# MercurialSDR_MISC.net
KiCad netlist of a schematic drawn in Altium Designer
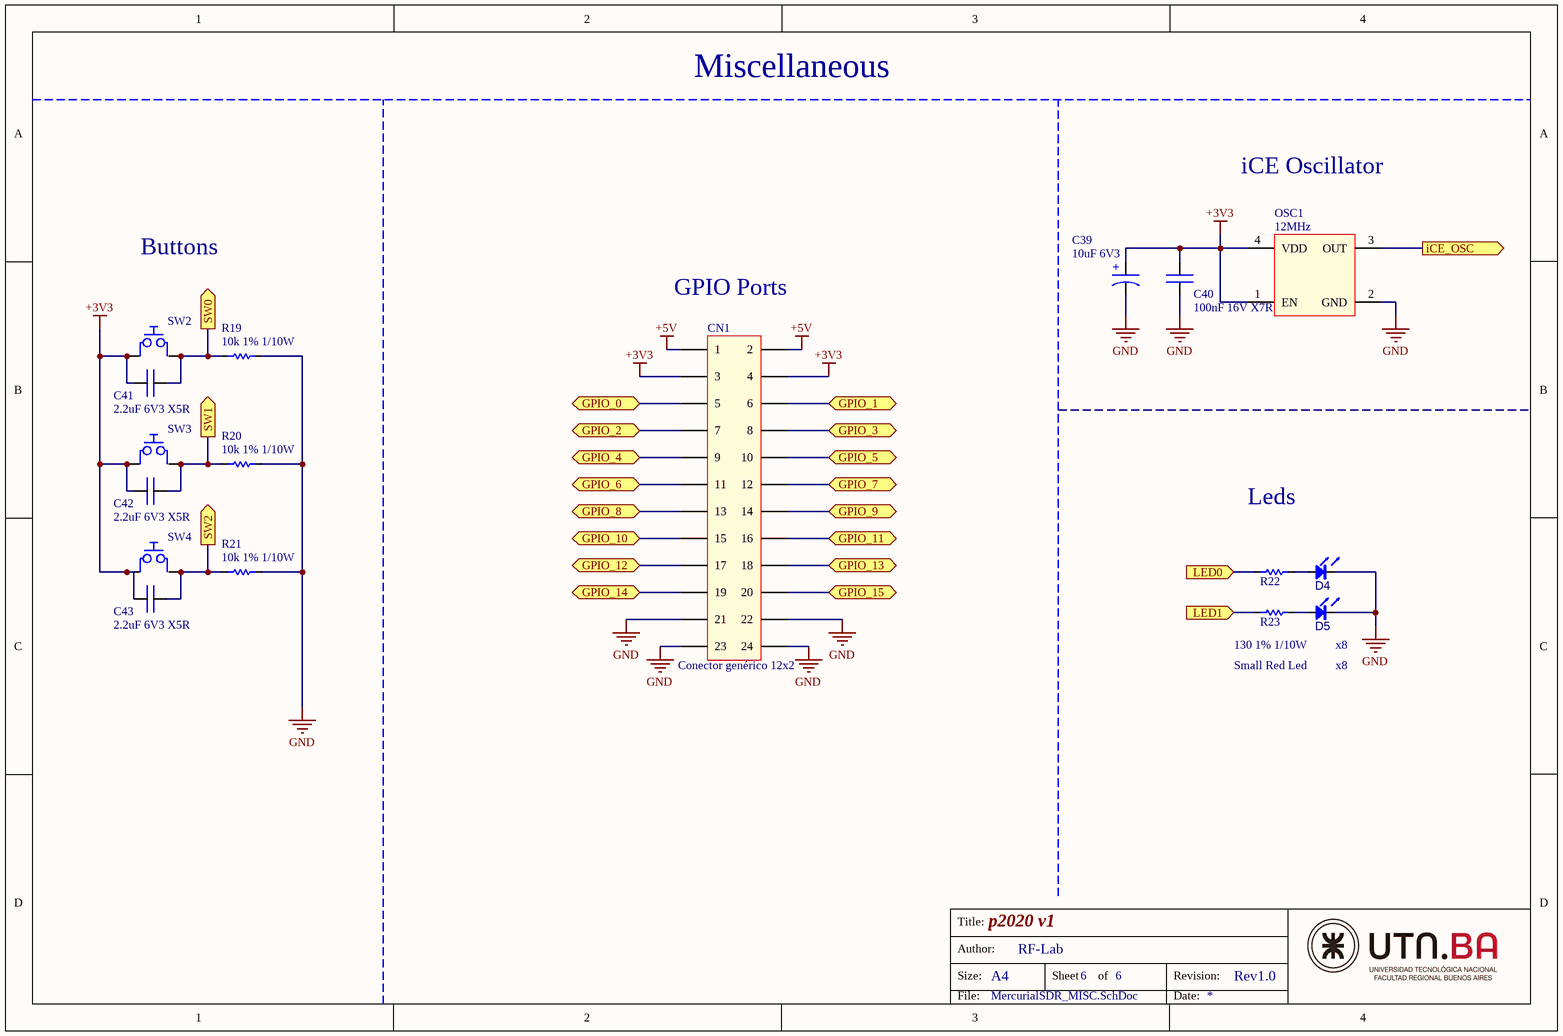
[diagram p0: MercurialSDR_MISC.SchDoc]

(export (version "E")
  (design (tool "Eeschema 10.0.6"))
  (components
    (comp (ref "C39")
      (value "10uF 6V3")
      (footprint "CAP_TANT_1206")
      (description "Capacitor polarizado")
      (fields (field (name "Comment") "10uF 6V3 - TAJA106K006RNJ"))
      (libsource (lib "MercurialSDR") (part "Cap Pol"))
    )
    (comp (ref "C40")
      (value "100nF 16V X7R")
      (footprint "CAP_0603")
      (description "Capacitor no polarizado")
      (fields
        (field (name "PART NUMBER") "CL10B104KO8NNNC")
        (field (name "Comment") "100nF 16V X7R - CL10B104KO8NNNC")
      )
      (libsource (lib "MercurialSDR") (part "Cap"))
    )
    (comp (ref "C41")
      (value "2.2uF 6V3 X5R")
      (footprint "CAP_0603")
      (description "Capacitor no polarizado")
      (fields (field (name "Comment") "2.2uF 6V3 X5R - CL10A225KQ8NNNC"))
      (libsource (lib "MercurialSDR") (part "Cap"))
    )
    (comp (ref "C42")
      (value "2.2uF 6V3 X5R")
      (footprint "CAP_0603")
      (description "Capacitor no polarizado")
      (fields
        (field (name "PART NUMBER") "CL10A225KQ8NNNC")
        (field (name "Comment") "2.2uF 6V3 X5R - CL10A225KQ8NNNC")
      )
      (libsource (lib "MercurialSDR") (part "Cap"))
    )
    (comp (ref "C43")
      (value "2.2uF 6V3 X5R")
      (footprint "CAP_0603")
      (description "Capacitor no polarizado")
      (fields
        (field (name "PART NUMBER") "CL10A225KQ8NNNC")
        (field (name "Comment") "2.2uF 6V3 X5R - CL10A225KQ8NNNC")
      )
      (libsource (lib "MercurialSDR") (part "Cap"))
    )
    (comp (ref "CN1")
      (value "Conector genérico 12x2")
      (footprint "CON_12x2")
      (fields (field (name "PART NUMBER") "6-534236-2") (field (name "Comment") "6-534236-2 // PPPC122LFBN"))
      (libsource (lib "MercurialSDR") (part "CN_12x2"))
    )
    (comp (ref "D4")
      (value "LTST-C190KRKT")
      (footprint "LED_0603")
      (description "Led_small")
      (libsource (lib "MercurialSDR") (part "Led_small"))
    )
    (comp (ref "D5")
      (value "LTST-C190KRKT")
      (footprint "LED_0603")
      (description "Led_small")
      (fields (field (name "COLOR") "Small Red Led"))
      (libsource (lib "MercurialSDR") (part "Led_small"))
    )
    (comp (ref "OSC1")
      (value "DSC6003JI2A-012.0000T")
      (footprint "VFLGA_2.5x2.0")
      (description "Oscilador de 4 terminales")
      (fields (field (name "FREQUENCY") "12MHz"))
      (libsource (lib "MercurialSDR") (part "Oscillator"))
    )
    (comp (ref "R19")
      (value "10k 1% 1/10W")
      (footprint "RES_0603")
      (description "Resistor")
      (fields (field (name "Comment") "10k 1% 1/10W - CR0603-FX-1002EAS"))
      (libsource (lib "MercurialSDR") (part "Res"))
    )
    (comp (ref "R20")
      (value "10k 1% 1/10W")
      (footprint "RES_0603")
      (description "Resistor")
      (fields (field (name "Comment") "10k 1% 1/10W - CR0603-FX-1002EAS"))
      (libsource (lib "MercurialSDR") (part "Res"))
    )
    (comp (ref "R21")
      (value "10k 1% 1/10W")
      (footprint "RES_0603")
      (description "Resistor")
      (fields (field (name "Comment") "10k 1% 1/10W - CR0603-FX-1002EAS"))
      (libsource (lib "MercurialSDR") (part "Res"))
    )
    (comp (ref "R22")
      (value "130 1% 1/10W - CR0603-FX-1300ELF")
      (footprint "RES_0603")
      (description "Resistor")
      (fields (field (name "POWER") "1/10W") (field (name "PART NUMBER") "CR0603-FX-1300ELF"))
      (libsource (lib "MercurialSDR") (part "Res"))
    )
    (comp (ref "R23")
      (value "130 1% 1/10W")
      (footprint "RES_0603")
      (description "Resistor")
      (fields (field (name "POWER") "1/10W") (field (name "PART NUMBER") "CR0603-FX-1300ELF"))
      (libsource (lib "MercurialSDR") (part "Res"))
    )
    (comp (ref "SW2")
      (value "PTS645SM43SMTR92 LFS")
      (footprint "SWITCH_6X6mm")
      (description "Pulsador")
      (libsource (lib "MercurialSDR") (part "Pulsador"))
    )
    (comp (ref "SW3")
      (value "PTS645SM43SMTR92 LFS")
      (footprint "SWITCH_6X6mm")
      (description "Pulsador")
      (libsource (lib "MercurialSDR") (part "Pulsador"))
    )
    (comp (ref "SW4")
      (value "PTS645SM43SMTR92 LFS")
      (footprint "SWITCH_6X6mm")
      (description "Pulsador")
      (libsource (lib "MercurialSDR") (part "Pulsador"))
    )
  )
  (nets
    (net (code "1") (name "+3V3") (class "Default")
      (node (ref "C39") (pin "1") (pinfunction "1_1") (pintype "passive"))
      (node (ref "C40") (pin "1") (pinfunction "1_1") (pintype "passive"))
      (node (ref "C41") (pin "1") (pinfunction "1_1") (pintype "passive"))
      (node (ref "C42") (pin "1") (pinfunction "1_1") (pintype "passive"))
      (node (ref "C43") (pin "1") (pinfunction "1_1") (pintype "passive"))
      (node (ref "CN1") (pin "3") (pinfunction "3_3") (pintype "passive"))
      (node (ref "CN1") (pin "4") (pinfunction "4_4") (pintype "passive"))
      (node (ref "OSC1") (pin "1") (pinfunction "EN_1") (pintype "passive"))
      (node (ref "OSC1") (pin "4") (pinfunction "VDD_4") (pintype "passive"))
      (node (ref "SW2") (pin "1") (pinfunction "1_1") (pintype "passive"))
      (node (ref "SW3") (pin "1") (pinfunction "1_1") (pintype "passive"))
      (node (ref "SW4") (pin "1") (pinfunction "1_1") (pintype "passive"))
    )
    (net (code "2") (name "+5V") (class "Default")
      (node (ref "CN1") (pin "1") (pinfunction "1_1") (pintype "passive"))
      (node (ref "CN1") (pin "2") (pinfunction "2_2") (pintype "passive"))
    )
    (net (code "3") (name "/GPIO_0") (class "Default")
      (node (ref "CN1") (pin "5") (pinfunction "5_5") (pintype "passive"))
    )
    (net (code "4") (name "/GPIO_1") (class "Default")
      (node (ref "CN1") (pin "6") (pinfunction "6_6") (pintype "passive"))
    )
    (net (code "5") (name "/GPIO_2") (class "Default")
      (node (ref "CN1") (pin "7") (pinfunction "7_7") (pintype "passive"))
    )
    (net (code "6") (name "/GPIO_3") (class "Default")
      (node (ref "CN1") (pin "8") (pinfunction "8_8") (pintype "passive"))
    )
    (net (code "7") (name "/GPIO_4") (class "Default")
      (node (ref "CN1") (pin "9") (pinfunction "9_9") (pintype "passive"))
    )
    (net (code "8") (name "/GPIO_5") (class "Default")
      (node (ref "CN1") (pin "10") (pinfunction "10_10") (pintype "passive"))
    )
    (net (code "9") (name "/GPIO_6") (class "Default")
      (node (ref "CN1") (pin "11") (pinfunction "11_11") (pintype "passive"))
    )
    (net (code "10") (name "/GPIO_7") (class "Default")
      (node (ref "CN1") (pin "12") (pinfunction "12_12") (pintype "passive"))
    )
    (net (code "11") (name "/GPIO_8") (class "Default")
      (node (ref "CN1") (pin "13") (pinfunction "13_13") (pintype "passive"))
    )
    (net (code "12") (name "/GPIO_9") (class "Default")
      (node (ref "CN1") (pin "14") (pinfunction "14_14") (pintype "passive"))
    )
    (net (code "13") (name "/GPIO_10") (class "Default")
      (node (ref "CN1") (pin "15") (pinfunction "15_15") (pintype "passive"))
    )
    (net (code "14") (name "/GPIO_11") (class "Default")
      (node (ref "CN1") (pin "16") (pinfunction "16_16") (pintype "passive"))
    )
    (net (code "15") (name "/GPIO_12") (class "Default")
      (node (ref "CN1") (pin "17") (pinfunction "17_17") (pintype "passive"))
    )
    (net (code "16") (name "/GPIO_13") (class "Default")
      (node (ref "CN1") (pin "18") (pinfunction "18_18") (pintype "passive"))
    )
    (net (code "17") (name "/GPIO_14") (class "Default")
      (node (ref "CN1") (pin "19") (pinfunction "19_19") (pintype "passive"))
    )
    (net (code "18") (name "/GPIO_15") (class "Default")
      (node (ref "CN1") (pin "20") (pinfunction "20_20") (pintype "passive"))
    )
    (net (code "19") (name "/LED0") (class "Default")
      (node (ref "R22") (pin "2") (pinfunction "2_2") (pintype "passive"))
    )
    (net (code "20") (name "/LED1") (class "Default")
      (node (ref "R23") (pin "2") (pinfunction "2_2") (pintype "passive"))
    )
    (net (code "21") (name "/SW0") (class "Default")
      (node (ref "C41") (pin "2") (pinfunction "2_2") (pintype "passive"))
      (node (ref "R19") (pin "2") (pinfunction "2_2") (pintype "passive"))
      (node (ref "SW2") (pin "4") (pinfunction "4_4") (pintype "passive"))
    )
    (net (code "22") (name "/SW1") (class "Default")
      (node (ref "C42") (pin "2") (pinfunction "2_2") (pintype "passive"))
      (node (ref "R20") (pin "2") (pinfunction "2_2") (pintype "passive"))
      (node (ref "SW3") (pin "4") (pinfunction "4_4") (pintype "passive"))
    )
    (net (code "23") (name "/SW2") (class "Default")
      (node (ref "C43") (pin "2") (pinfunction "2_2") (pintype "passive"))
      (node (ref "R21") (pin "2") (pinfunction "2_2") (pintype "passive"))
      (node (ref "SW4") (pin "4") (pinfunction "4_4") (pintype "passive"))
    )
    (net (code "24") (name "/iCE_OSC") (class "Default")
      (node (ref "OSC1") (pin "3") (pinfunction "OUT_3") (pintype "passive"))
    )
    (net (code "25") (name "GND") (class "Default")
      (node (ref "C39") (pin "2") (pinfunction "2_2") (pintype "passive"))
      (node (ref "C40") (pin "2") (pinfunction "2_2") (pintype "passive"))
      (node (ref "CN1") (pin "21") (pinfunction "21_21") (pintype "passive"))
      (node (ref "CN1") (pin "22") (pinfunction "22_22") (pintype "passive"))
      (node (ref "CN1") (pin "23") (pinfunction "23_23") (pintype "passive"))
      (node (ref "CN1") (pin "24") (pinfunction "24_24") (pintype "passive"))
      (node (ref "D4") (pin "2") (pinfunction "K_2") (pintype "passive"))
      (node (ref "D5") (pin "2") (pinfunction "K_2") (pintype "passive"))
      (node (ref "OSC1") (pin "2") (pinfunction "GND_2") (pintype "passive"))
      (node (ref "R19") (pin "1") (pinfunction "1_1") (pintype "passive"))
      (node (ref "R20") (pin "1") (pinfunction "1_1") (pintype "passive"))
      (node (ref "R21") (pin "1") (pinfunction "1_1") (pintype "passive"))
    )
    (net (code "26") (name "Net-(D4-A)") (class "Default")
      (node (ref "D4") (pin "1") (pinfunction "A_1") (pintype "passive"))
      (node (ref "R22") (pin "1") (pinfunction "1_1") (pintype "passive"))
    )
    (net (code "27") (name "Net-(D5-A)") (class "Default")
      (node (ref "D5") (pin "1") (pinfunction "A_1") (pintype "passive"))
      (node (ref "R23") (pin "1") (pinfunction "1_1") (pintype "passive"))
    )
    (net (code "28") (name "unconnected-(SW2-Pad2)") (class "Default")
      (node (ref "SW2") (pin "2") (pinfunction "2_2") (pintype "passive"))
    )
    (net (code "29") (name "unconnected-(SW2-Pad3)") (class "Default")
      (node (ref "SW2") (pin "3") (pinfunction "3_3") (pintype "passive"))
    )
    (net (code "30") (name "unconnected-(SW3-Pad2)") (class "Default")
      (node (ref "SW3") (pin "2") (pinfunction "2_2") (pintype "passive"))
    )
    (net (code "31") (name "unconnected-(SW3-Pad3)") (class "Default")
      (node (ref "SW3") (pin "3") (pinfunction "3_3") (pintype "passive"))
    )
    (net (code "32") (name "unconnected-(SW4-Pad2)") (class "Default")
      (node (ref "SW4") (pin "2") (pinfunction "2_2") (pintype "passive"))
    )
    (net (code "33") (name "unconnected-(SW4-Pad3)") (class "Default")
      (node (ref "SW4") (pin "3") (pinfunction "3_3") (pintype "passive"))
    )
  )
)
